# BigSwitch.net
KiCad netlist of a schematic drawn in Altium Designer
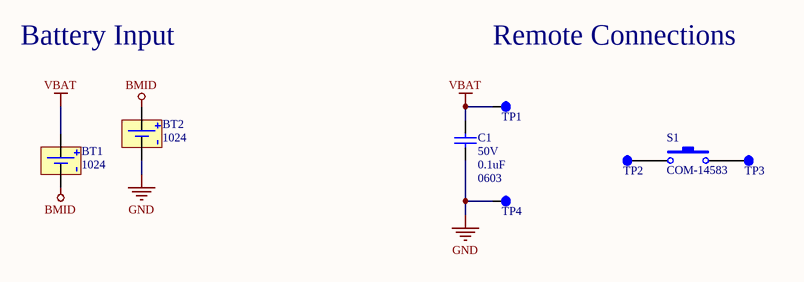
[diagram p0: BigSwitch.SchDoc]

(export (version "E")
  (design (tool "Eeschema 10.0.6"))
  (components
    (comp (ref "BT1")
      (value "1024")
      (footprint "Footprint_Battery:1024")
      (description "HOLDER BATTERY AA SMD")
      (fields (field (name "MANUFACTURER") "Keystone Electronics"))
      (libsource (lib "Schematic_Battery") (part "1024"))
    )
    (comp (ref "BT2")
      (value "1024")
      (footprint "Footprint_Battery:1024")
      (description "HOLDER BATTERY AA SMD")
      (fields (field (name "MANUFACTURER") "Keystone Electronics"))
      (libsource (lib "Schematic_Battery") (part "1024"))
    )
    (comp (ref "C1")
      (value "0.1uF")
      (footprint "Footprint_Capacitor:CAPC1608X09N")
      (description "General purpose capacitor")
      (fields
        (field (name "RATED VOLTAGE") "50V")
        (field (name "PACKAGE") "0603")
        (field (name "Comment") "Capacitor")
      )
      (libsource (lib "Schematic_Generic") (part "Capacitor"))
    )
    (comp (ref "S1")
      (value "COM-14583")
      (footprint "Footprint_Switch:CPG151101D228")
      (description "Novelkeys Big Switch - Tactile")
      (fields (field (name "MANUFACTURER") "SparkFun"))
      (libsource (lib "Schematic_Switch") (part "COM-14583"))
    )
    (comp (ref "TP1")
      (value "Test Point")
      (footprint "Footprint_Testpoint:TP_RECTANGULAR_1.5X2MM")
      (description "General purpose test point")
      (libsource (lib "Schematic_Generic") (part "Test Point"))
    )
    (comp (ref "TP2")
      (value "Test Point")
      (footprint "Footprint_Testpoint:TP_CIRCULAR_SMD_1MM")
      (description "General purpose test point")
      (libsource (lib "Schematic_Generic") (part "Test Point"))
    )
    (comp (ref "TP3")
      (value "Test Point")
      (footprint "Footprint_Testpoint:TP_CIRCULAR_SMD_1MM")
      (description "General purpose test point")
      (libsource (lib "Schematic_Generic") (part "Test Point"))
    )
    (comp (ref "TP4")
      (value "Test Point")
      (footprint "Footprint_Testpoint:TP_RECTANGULAR_1.5X2MM")
      (description "General purpose test point")
      (libsource (lib "Schematic_Generic") (part "Test Point"))
    )
  )
  (nets
    (net (code "1") (name "BMID") (class "Default")
      (node (ref "BT1") (pin "B-") (pinfunction "B-_B-") (pintype "power_in"))
      (node (ref "BT2") (pin "B+") (pinfunction "B+_B+") (pintype "power_in"))
    )
    (net (code "2") (name "GND") (class "Default")
      (node (ref "BT2") (pin "B-") (pinfunction "B-_B-") (pintype "power_in"))
      (node (ref "C1") (pin "1") (pinfunction "1_1") (pintype "passive"))
      (node (ref "TP4") (pin "1") (pintype "passive"))
    )
    (net (code "3") (name "Net-(S1-Pad1)") (class "Default")
      (node (ref "S1") (pin "1") (pinfunction "1_1") (pintype "passive"))
      (node (ref "TP2") (pin "1") (pintype "passive"))
    )
    (net (code "4") (name "Net-(S1-Pad2)") (class "Default")
      (node (ref "S1") (pin "2") (pinfunction "2_2") (pintype "passive"))
      (node (ref "TP3") (pin "1") (pintype "passive"))
    )
    (net (code "5") (name "VBAT") (class "Default")
      (node (ref "BT1") (pin "B+") (pinfunction "B+_B+") (pintype "power_in"))
      (node (ref "C1") (pin "2") (pinfunction "2_2") (pintype "passive"))
      (node (ref "TP1") (pin "1") (pintype "passive"))
    )
  )
)
